# VFan.net
KiCad netlist of a schematic drawn in Altium Designer
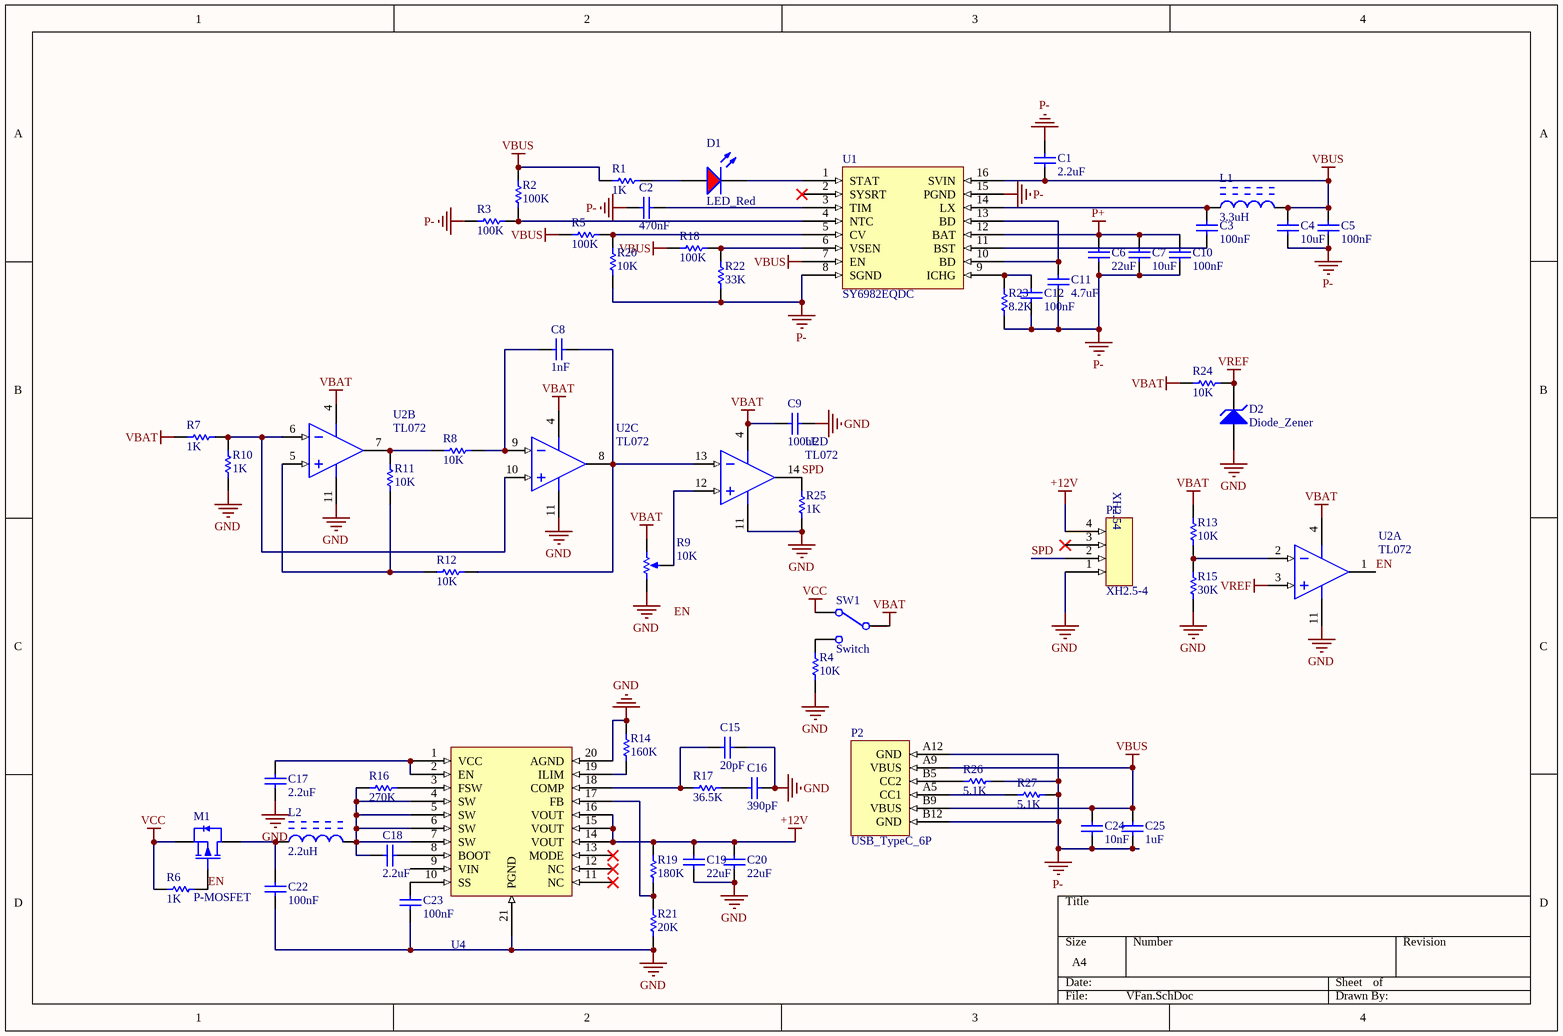
[diagram p0: VFan.SchDoc]

(export (version "E")
  (design (tool "Eeschema 10.0.6"))
  (components
    (comp (ref "C1") (value "2.2uF") (footprint "SMC_0805") (libsource (lib "Common") (part "Cap Ceramic")))
    (comp (ref "C2") (value "470nF") (footprint "SMC_0402") (libsource (lib "Common") (part "Cap Ceramic")))
    (comp (ref "C3") (value "100nF") (footprint "SMC_0402") (libsource (lib "Common") (part "Cap Ceramic")))
    (comp (ref "C4") (value "10uF") (footprint "SMC_0805") (libsource (lib "Common") (part "Cap Ceramic")))
    (comp (ref "C5") (value "100nF") (footprint "SMC_0603") (libsource (lib "Common") (part "Cap Ceramic")))
    (comp (ref "C6") (value "22uF") (footprint "SMC_0805") (libsource (lib "Common") (part "Cap Ceramic")))
    (comp (ref "C7") (value "10uF") (footprint "SMC_0805") (libsource (lib "Common") (part "Cap Ceramic")))
    (comp (ref "C8") (value "1nF") (footprint "SMC_0402") (libsource (lib "Common") (part "Cap Ceramic")))
    (comp (ref "C9") (value "100nF") (footprint "SMC_0402") (libsource (lib "Common") (part "Cap Ceramic")))
    (comp (ref "C10") (value "100nF") (footprint "SMC_0603") (libsource (lib "Common") (part "Cap Ceramic")))
    (comp (ref "C11") (value "4.7uF") (footprint "SMC_0805") (libsource (lib "Common") (part "Cap Ceramic")))
    (comp (ref "C12") (value "100nF") (footprint "SMC_0603") (libsource (lib "Common") (part "Cap Ceramic")))
    (comp (ref "C15") (value "20pF") (footprint "SMC_0402") (libsource (lib "Common") (part "Cap Ceramic")))
    (comp (ref "C16") (value "390pF") (footprint "SMC_0402") (libsource (lib "Common") (part "Cap Ceramic")))
    (comp (ref "C17") (value "2.2uF") (footprint "SMC_0603") (libsource (lib "Common") (part "Cap Ceramic")))
    (comp (ref "C18") (value "2.2uF") (footprint "SMC_0603") (libsource (lib "Common") (part "Cap Ceramic")))
    (comp (ref "C19") (value "22uF") (footprint "SMC_1210") (libsource (lib "Common") (part "Cap Ceramic")))
    (comp (ref "C20") (value "22uF") (footprint "SMC_1210") (libsource (lib "Common") (part "Cap Ceramic")))
    (comp (ref "C22") (value "100nF") (footprint "SMC_0402") (libsource (lib "Common") (part "Cap Ceramic")))
    (comp (ref "C23") (value "100nF") (footprint "SMC_0402") (libsource (lib "Common") (part "Cap Ceramic")))
    (comp (ref "C24") (value "10nF") (footprint "SMC_0402") (libsource (lib "Common") (part "Cap Ceramic")))
    (comp (ref "C25") (value "1uF") (footprint "SMC_0402") (libsource (lib "Common") (part "Cap Ceramic")))
    (comp (ref "D1") (value "LED_Red") (footprint "THLED_3mm") (libsource (lib "Common") (part "LED_Red")))
    (comp (ref "D2")
      (value "Diode_Zener")
      (footprint "SOD-123")
      (libsource (lib "Common") (part "Diode_Zener"))
    )
    (comp (ref "L1")
      (value "3.3uH")
      (footprint "SML_4.1x4.6")
      (libsource (lib "Common") (part "Inductor_Ferrite SMT"))
    )
    (comp (ref "L2")
      (value "2.2uH")
      (footprint "SML_7.4x6.6")
      (libsource (lib "Common") (part "Inductor_Ferrite SMT"))
    )
    (comp (ref "M1")
      (value "P-MOSFET")
      (footprint "SOIC127P600X175-8N")
      (libsource (lib "BJT_MOSFET") (part "P-MOSFET"))
    )
    (comp (ref "P1") (value "XH2.5-4") (footprint "XH2.54-4S") (libsource (lib "Connector") (part "XH2.5-4")))
    (comp (ref "P2")
      (value "USB_TypeC_6P")
      (footprint "USB_TypeC_6P")
      (libsource (lib "Connector") (part "USB_TypeC_6P"))
    )
    (comp (ref "R1") (value "1K") (footprint "SMR_0402") (libsource (lib "Common") (part "Res SMT")))
    (comp (ref "R2") (value "100K") (footprint "SMR_0402") (libsource (lib "Common") (part "Res SMT")))
    (comp (ref "R3") (value "100K") (footprint "SMR_0402") (libsource (lib "Common") (part "Res SMT")))
    (comp (ref "R4") (value "10K") (footprint "SMR_0402") (libsource (lib "Common") (part "Res SMT")))
    (comp (ref "R5") (value "100K") (footprint "SMR_0402") (libsource (lib "Common") (part "Res SMT")))
    (comp (ref "R6") (value "1K") (footprint "SMR_0402") (libsource (lib "Common") (part "Res SMT")))
    (comp (ref "R7") (value "1K") (footprint "SMR_0402") (libsource (lib "Common") (part "Res SMT")))
    (comp (ref "R8") (value "10K") (footprint "SMR_0402") (libsource (lib "Common") (part "Res SMT")))
    (comp (ref "R9") (value "10K") (footprint "RV09032") (libsource (lib "Common") (part "Res Var")))
    (comp (ref "R10") (value "1K") (footprint "SMR_0402") (libsource (lib "Common") (part "Res SMT")))
    (comp (ref "R11") (value "10K") (footprint "SMR_0402") (libsource (lib "Common") (part "Res SMT")))
    (comp (ref "R12") (value "10K") (footprint "SMR_0402") (libsource (lib "Common") (part "Res SMT")))
    (comp (ref "R13") (value "10K") (footprint "SMR_0402") (libsource (lib "Common") (part "Res SMT")))
    (comp (ref "R14") (value "160K") (footprint "SMR_0402") (libsource (lib "Common") (part "Res SMT")))
    (comp (ref "R15") (value "30K") (footprint "SMR_0402") (libsource (lib "Common") (part "Res SMT")))
    (comp (ref "R16") (value "270K") (footprint "SMR_0402") (libsource (lib "Common") (part "Res SMT")))
    (comp (ref "R17") (value "36.5K") (footprint "SMR_0402") (libsource (lib "Common") (part "Res SMT")))
    (comp (ref "R18") (value "100K") (footprint "SMR_0402") (libsource (lib "Common") (part "Res SMT")))
    (comp (ref "R19") (value "180K") (footprint "SMR_0402") (libsource (lib "Common") (part "Res SMT")))
    (comp (ref "R20") (value "10K") (footprint "SMR_0402") (libsource (lib "Common") (part "Res SMT")))
    (comp (ref "R21") (value "20K") (footprint "SMR_0402") (libsource (lib "Common") (part "Res SMT")))
    (comp (ref "R22") (value "33K") (footprint "SMR_0402") (libsource (lib "Common") (part "Res SMT")))
    (comp (ref "R23") (value "8.2K") (footprint "SMR_0402") (libsource (lib "Common") (part "Res SMT")))
    (comp (ref "R24") (value "10K") (footprint "SMR_0402") (libsource (lib "Common") (part "Res SMT")))
    (comp (ref "R25") (value "1K") (footprint "SMR_0402") (libsource (lib "Common") (part "Res SMT")))
    (comp (ref "R26") (value "5.1K") (footprint "SMR_0402") (libsource (lib "Common") (part "Res SMT")))
    (comp (ref "R27") (value "5.1K") (footprint "SMR_0402") (libsource (lib "Common") (part "Res SMT")))
    (comp (ref "SW1") (value "Switch") (footprint "Switch") (libsource (lib "Button_Switch") (part "Switch")))
    (comp (ref "U1")
      (value "SY6982EQDC")
      (footprint "SY6982EQDC")
      (libsource (lib "Charger") (part "SY6982EQDC"))
    )
    (comp (ref "U2")
      (value "TL072")
      (footprint "TSOP65P640X120-14N")
      (libsource (lib "OpAmp") (part "OPA4376"))
    )
    (comp (ref "U4")
      (value "Buck Boost Converter")
      (footprint "QFN50P350X450X100_HS-21N")
      (libsource (lib "PowerManagement") (part "TPS61088"))
    )
  )
  (nets
    (net (code "1") (name "+12V") (class "Default")
      (node (ref "C19") (pin "2") (pinfunction "2_2") (pintype "passive"))
      (node (ref "C20") (pin "2") (pinfunction "2_2") (pintype "passive"))
      (node (ref "P1") (pin "4") (pintype "input"))
      (node (ref "R19") (pin "2") (pinfunction "2_2") (pintype "passive"))
      (node (ref "U4") (pin "14") (pinfunction "VOUT_14") (pintype "input"))
      (node (ref "U4") (pin "15") (pinfunction "VOUT_15") (pintype "input"))
      (node (ref "U4") (pin "16") (pinfunction "VOUT_16") (pintype "input"))
    )
    (net (code "2") (name "/EN") (class "Default")
      (node (ref "M1") (pin "G") (pinfunction "G_G") (pintype "passive"))
      (node (ref "R6") (pin "1") (pinfunction "1_1") (pintype "passive"))
      (node (ref "U2") (pin "1") (pinfunction "OUT_1") (pintype "open_collector"))
    )
    (net (code "3") (name "/SPD") (class "Default")
      (node (ref "P1") (pin "2") (pintype "input"))
      (node (ref "R25") (pin "1") (pinfunction "1_1") (pintype "passive"))
      (node (ref "U2") (pin "14") (pinfunction "OUT_14") (pintype "open_collector"))
    )
    (net (code "4") (name "GND") (class "Default")
      (node (ref "C15") (pin "2") (pinfunction "2_2") (pintype "passive"))
      (node (ref "C16") (pin "2") (pinfunction "2_2") (pintype "passive"))
      (node (ref "C17") (pin "1") (pinfunction "1_1") (pintype "passive"))
      (node (ref "C19") (pin "1") (pinfunction "1_1") (pintype "passive"))
      (node (ref "C20") (pin "1") (pinfunction "1_1") (pintype "passive"))
      (node (ref "C22") (pin "2") (pinfunction "2_2") (pintype "passive"))
      (node (ref "C23") (pin "2") (pinfunction "2_2") (pintype "passive"))
      (node (ref "C9") (pin "2") (pinfunction "2_2") (pintype "passive"))
      (node (ref "D2") (pin "A") (pinfunction "A_A") (pintype "passive"))
      (node (ref "P1") (pin "1") (pintype "input"))
      (node (ref "R10") (pin "1") (pinfunction "1_1") (pintype "passive"))
      (node (ref "R14") (pin "2") (pinfunction "2_2") (pintype "passive"))
      (node (ref "R15") (pin "1") (pinfunction "1_1") (pintype "passive"))
      (node (ref "R21") (pin "1") (pinfunction "1_1") (pintype "passive"))
      (node (ref "R25") (pin "2") (pinfunction "2_2") (pintype "passive"))
      (node (ref "R4") (pin "1") (pinfunction "1_1") (pintype "passive"))
      (node (ref "R9") (pin "1") (pinfunction "TOP_1") (pintype "passive"))
      (node (ref "U2") (pin "11") (pinfunction "V-_11") (pintype "power_in"))
      (node (ref "U4") (pin "20") (pinfunction "AGND_20") (pintype "input"))
      (node (ref "U4") (pin "21") (pinfunction "PGND_21") (pintype "input"))
    )
    (net (code "5") (name "Net-(C11-Pad2)") (class "Default")
      (node (ref "C11") (pin "2") (pinfunction "2_2") (pintype "passive"))
      (node (ref "U1") (pin "10") (pinfunction "BD_10") (pintype "input"))
      (node (ref "U1") (pin "13") (pinfunction "BD_13") (pintype "input"))
    )
    (net (code "6") (name "Net-(C16-Pad1)") (class "Default")
      (node (ref "C16") (pin "1") (pinfunction "1_1") (pintype "passive"))
      (node (ref "R17") (pin "1") (pinfunction "1_1") (pintype "passive"))
    )
    (net (code "7") (name "Net-(C18-Pad2)") (class "Default")
      (node (ref "C18") (pin "2") (pinfunction "2_2") (pintype "passive"))
      (node (ref "L2") (pin "2") (pinfunction "2_2") (pintype "passive"))
      (node (ref "R16") (pin "1") (pinfunction "1_1") (pintype "passive"))
      (node (ref "U4") (pin "4") (pinfunction "SW_4") (pintype "input"))
      (node (ref "U4") (pin "5") (pinfunction "SW_5") (pintype "input"))
      (node (ref "U4") (pin "6") (pinfunction "SW_6") (pintype "input"))
      (node (ref "U4") (pin "7") (pinfunction "SW_7") (pintype "input"))
    )
    (net (code "8") (name "Net-(C22-Pad1)") (class "Default")
      (node (ref "C22") (pin "1") (pinfunction "1_1") (pintype "passive"))
      (node (ref "L2") (pin "1") (pinfunction "1_1") (pintype "passive"))
      (node (ref "M1") (pin "D") (pinfunction "D_D") (pintype "passive"))
    )
    (net (code "9") (name "Net-(D1-PadA)") (class "Default")
      (node (ref "D1") (pin "A") (pinfunction "A_A") (pintype "passive"))
      (node (ref "R1") (pin "1") (pinfunction "1_1") (pintype "passive"))
    )
    (net (code "10") (name "Net-(P2-CC1)") (class "Default")
      (node (ref "P2") (pin "A5") (pinfunction "CC1_A5") (pintype "input"))
      (node (ref "R27") (pin "1") (pinfunction "1_1") (pintype "passive"))
    )
    (net (code "11") (name "Net-(P2-CC2)") (class "Default")
      (node (ref "P2") (pin "B5") (pinfunction "CC2_B5") (pintype "input"))
      (node (ref "R26") (pin "1") (pinfunction "1_1") (pintype "passive"))
    )
    (net (code "12") (name "Net-(R4-Pad2)") (class "Default")
      (node (ref "R4") (pin "2") (pinfunction "2_2") (pintype "passive"))
      (node (ref "SW1") (pin "3") (pinfunction "3_3") (pintype "passive"))
    )
    (net (code "13") (name "Net-(R9-TAP)") (class "Default")
      (node (ref "R9") (pin "2") (pinfunction "TAP_2") (pintype "passive"))
      (node (ref "U2") (pin "12") (pinfunction "IN+_12") (pintype "input"))
    )
    (net (code "14") (name "Net-(U1-BST)") (class "Default")
      (node (ref "C3") (pin "1") (pinfunction "1_1") (pintype "passive"))
      (node (ref "U1") (pin "11") (pinfunction "BST_11") (pintype "input"))
    )
    (net (code "15") (name "Net-(U1-CV)") (class "Default")
      (node (ref "R20") (pin "2") (pinfunction "2_2") (pintype "passive"))
      (node (ref "R5") (pin "1") (pinfunction "1_1") (pintype "passive"))
      (node (ref "U1") (pin "5") (pinfunction "CV_5") (pintype "input"))
    )
    (net (code "16") (name "Net-(U1-ICHG)") (class "Default")
      (node (ref "C12") (pin "2") (pinfunction "2_2") (pintype "passive"))
      (node (ref "R23") (pin "2") (pinfunction "2_2") (pintype "passive"))
      (node (ref "U1") (pin "9") (pinfunction "ICHG_9") (pintype "input"))
    )
    (net (code "17") (name "Net-(U1-LX)") (class "Default")
      (node (ref "C3") (pin "2") (pinfunction "2_2") (pintype "passive"))
      (node (ref "L1") (pin "1") (pinfunction "1_1") (pintype "passive"))
      (node (ref "U1") (pin "14") (pinfunction "LX_14") (pintype "input"))
    )
    (net (code "18") (name "Net-(U1-NTC)") (class "Default")
      (node (ref "R2") (pin "1") (pinfunction "1_1") (pintype "passive"))
      (node (ref "R3") (pin "2") (pinfunction "2_2") (pintype "passive"))
      (node (ref "U1") (pin "4") (pinfunction "NTC_4") (pintype "input"))
    )
    (net (code "19") (name "Net-(U1-STAT)") (class "Default")
      (node (ref "D1") (pin "K") (pinfunction "K_K") (pintype "passive"))
      (node (ref "U1") (pin "1") (pinfunction "STAT_1") (pintype "input"))
    )
    (net (code "20") (name "Net-(U1-TIM)") (class "Default")
      (node (ref "C2") (pin "2") (pinfunction "2_2") (pintype "passive"))
      (node (ref "U1") (pin "3") (pinfunction "TIM_3") (pintype "input"))
    )
    (net (code "21") (name "Net-(U1-VSEN)") (class "Default")
      (node (ref "R18") (pin "1") (pinfunction "1_1") (pintype "passive"))
      (node (ref "R22") (pin "2") (pinfunction "2_2") (pintype "passive"))
      (node (ref "U1") (pin "6") (pinfunction "VSEN_6") (pintype "input"))
    )
    (net (code "22") (name "Net-(U2A-IN-)") (class "Default")
      (node (ref "R13") (pin "1") (pinfunction "1_1") (pintype "passive"))
      (node (ref "R15") (pin "2") (pinfunction "2_2") (pintype "passive"))
      (node (ref "U2") (pin "2") (pinfunction "IN-_2") (pintype "input"))
    )
    (net (code "23") (name "Net-(U2B-IN+)") (class "Default")
      (node (ref "R11") (pin "1") (pinfunction "1_1") (pintype "passive"))
      (node (ref "R12") (pin "1") (pinfunction "1_1") (pintype "passive"))
      (node (ref "U2") (pin "5") (pinfunction "IN+_5") (pintype "input"))
    )
    (net (code "24") (name "Net-(U2B-IN-)") (class "Default")
      (node (ref "R10") (pin "2") (pinfunction "2_2") (pintype "passive"))
      (node (ref "R7") (pin "1") (pinfunction "1_1") (pintype "passive"))
      (node (ref "U2") (pin "10") (pinfunction "IN+_10") (pintype "input"))
      (node (ref "U2") (pin "6") (pinfunction "IN-_6") (pintype "input"))
    )
    (net (code "25") (name "Net-(U2B-OUT)") (class "Default")
      (node (ref "R11") (pin "2") (pinfunction "2_2") (pintype "passive"))
      (node (ref "R8") (pin "1") (pinfunction "1_1") (pintype "passive"))
      (node (ref "U2") (pin "7") (pinfunction "OUT_7") (pintype "open_collector"))
    )
    (net (code "26") (name "Net-(U2C-IN-)") (class "Default")
      (node (ref "C8") (pin "1") (pinfunction "1_1") (pintype "passive"))
      (node (ref "R8") (pin "2") (pinfunction "2_2") (pintype "passive"))
      (node (ref "U2") (pin "9") (pinfunction "IN-_9") (pintype "input"))
    )
    (net (code "27") (name "Net-(U2C-OUT)") (class "Default")
      (node (ref "C8") (pin "2") (pinfunction "2_2") (pintype "passive"))
      (node (ref "R12") (pin "2") (pinfunction "2_2") (pintype "passive"))
      (node (ref "U2") (pin "13") (pinfunction "IN-_13") (pintype "input"))
      (node (ref "U2") (pin "8") (pinfunction "OUT_8") (pintype "open_collector"))
    )
    (net (code "28") (name "Net-(U4-BOOT)") (class "Default")
      (node (ref "C18") (pin "1") (pinfunction "1_1") (pintype "passive"))
      (node (ref "U4") (pin "8") (pinfunction "BOOT_8") (pintype "input"))
    )
    (net (code "29") (name "Net-(U4-COMP)") (class "Default")
      (node (ref "C15") (pin "1") (pinfunction "1_1") (pintype "passive"))
      (node (ref "R17") (pin "2") (pinfunction "2_2") (pintype "passive"))
      (node (ref "U4") (pin "18") (pinfunction "COMP_18") (pintype "input"))
    )
    (net (code "30") (name "Net-(U4-EN)") (class "Default")
      (node (ref "C17") (pin "2") (pinfunction "2_2") (pintype "passive"))
      (node (ref "U4") (pin "1") (pinfunction "VCC_1") (pintype "input"))
      (node (ref "U4") (pin "2") (pinfunction "EN_2") (pintype "input"))
    )
    (net (code "31") (name "Net-(U4-FB)") (class "Default")
      (node (ref "R19") (pin "1") (pinfunction "1_1") (pintype "passive"))
      (node (ref "R21") (pin "2") (pinfunction "2_2") (pintype "passive"))
      (node (ref "U4") (pin "17") (pinfunction "FB_17") (pintype "input"))
    )
    (net (code "32") (name "Net-(U4-FSW)") (class "Default")
      (node (ref "R16") (pin "2") (pinfunction "2_2") (pintype "passive"))
      (node (ref "U4") (pin "3") (pinfunction "FSW_3") (pintype "input"))
    )
    (net (code "33") (name "Net-(U4-ILIM)") (class "Default")
      (node (ref "R14") (pin "1") (pinfunction "1_1") (pintype "passive"))
      (node (ref "U4") (pin "19") (pinfunction "ILIM_19") (pintype "input"))
    )
    (net (code "34") (name "Net-(U4-SS)") (class "Default")
      (node (ref "C23") (pin "1") (pinfunction "1_1") (pintype "passive"))
      (node (ref "U4") (pin "10") (pinfunction "SS_10") (pintype "input"))
    )
    (net (code "35") (name "P+") (class "Default")
      (node (ref "C10") (pin "2") (pinfunction "2_2") (pintype "passive"))
      (node (ref "C6") (pin "2") (pinfunction "2_2") (pintype "passive"))
      (node (ref "C7") (pin "2") (pinfunction "2_2") (pintype "passive"))
      (node (ref "U1") (pin "12") (pinfunction "BAT_12") (pintype "input"))
    )
    (net (code "36") (name "P-") (class "Default")
      (node (ref "C1") (pin "2") (pinfunction "2_2") (pintype "passive"))
      (node (ref "C10") (pin "1") (pinfunction "1_1") (pintype "passive"))
      (node (ref "C11") (pin "1") (pinfunction "1_1") (pintype "passive"))
      (node (ref "C12") (pin "1") (pinfunction "1_1") (pintype "passive"))
      (node (ref "C2") (pin "1") (pinfunction "1_1") (pintype "passive"))
      (node (ref "C24") (pin "1") (pinfunction "1_1") (pintype "passive"))
      (node (ref "C25") (pin "1") (pinfunction "1_1") (pintype "passive"))
      (node (ref "C4") (pin "1") (pinfunction "1_1") (pintype "passive"))
      (node (ref "C5") (pin "1") (pinfunction "1_1") (pintype "passive"))
      (node (ref "C6") (pin "1") (pinfunction "1_1") (pintype "passive"))
      (node (ref "C7") (pin "1") (pinfunction "1_1") (pintype "passive"))
      (node (ref "P2") (pin "A12") (pinfunction "GND_A12") (pintype "input"))
      (node (ref "P2") (pin "B12") (pinfunction "GND_B12") (pintype "input"))
      (node (ref "R20") (pin "1") (pinfunction "1_1") (pintype "passive"))
      (node (ref "R22") (pin "1") (pinfunction "1_1") (pintype "passive"))
      (node (ref "R23") (pin "1") (pinfunction "1_1") (pintype "passive"))
      (node (ref "R26") (pin "2") (pinfunction "2_2") (pintype "passive"))
      (node (ref "R27") (pin "2") (pinfunction "2_2") (pintype "passive"))
      (node (ref "R3") (pin "1") (pinfunction "1_1") (pintype "passive"))
      (node (ref "U1") (pin "15") (pinfunction "PGND_15") (pintype "input"))
      (node (ref "U1") (pin "8") (pinfunction "SGND_8") (pintype "input"))
    )
    (net (code "37") (name "VBAT") (class "Default")
      (node (ref "C9") (pin "1") (pinfunction "1_1") (pintype "passive"))
      (node (ref "R13") (pin "2") (pinfunction "2_2") (pintype "passive"))
      (node (ref "R24") (pin "2") (pinfunction "2_2") (pintype "passive"))
      (node (ref "R7") (pin "2") (pinfunction "2_2") (pintype "passive"))
      (node (ref "R9") (pin "3") (pinfunction "BOT_3") (pintype "passive"))
      (node (ref "SW1") (pin "1") (pinfunction "1_1") (pintype "passive"))
      (node (ref "U2") (pin "4") (pinfunction "V+_4") (pintype "power_in"))
    )
    (net (code "38") (name "VBUS") (class "Default")
      (node (ref "C1") (pin "1") (pinfunction "1_1") (pintype "passive"))
      (node (ref "C24") (pin "2") (pinfunction "2_2") (pintype "passive"))
      (node (ref "C25") (pin "2") (pinfunction "2_2") (pintype "passive"))
      (node (ref "C4") (pin "2") (pinfunction "2_2") (pintype "passive"))
      (node (ref "C5") (pin "2") (pinfunction "2_2") (pintype "passive"))
      (node (ref "L1") (pin "2") (pinfunction "2_2") (pintype "passive"))
      (node (ref "P2") (pin "A9") (pinfunction "VBUS_A9") (pintype "input"))
      (node (ref "P2") (pin "B9") (pinfunction "VBUS_B9") (pintype "input"))
      (node (ref "R1") (pin "2") (pinfunction "2_2") (pintype "passive"))
      (node (ref "R18") (pin "2") (pinfunction "2_2") (pintype "passive"))
      (node (ref "R2") (pin "2") (pinfunction "2_2") (pintype "passive"))
      (node (ref "R5") (pin "2") (pinfunction "2_2") (pintype "passive"))
      (node (ref "U1") (pin "16") (pinfunction "SVIN_16") (pintype "input"))
      (node (ref "U1") (pin "7") (pinfunction "EN_7") (pintype "input"))
    )
    (net (code "39") (name "VCC") (class "Default")
      (node (ref "M1") (pin "S") (pinfunction "S_S") (pintype "passive"))
      (node (ref "R6") (pin "2") (pinfunction "2_2") (pintype "passive"))
      (node (ref "SW1") (pin "2") (pinfunction "2_2") (pintype "passive"))
    )
    (net (code "40") (name "VREF") (class "Default")
      (node (ref "D2") (pin "K") (pinfunction "K_K") (pintype "passive"))
      (node (ref "R24") (pin "1") (pinfunction "1_1") (pintype "passive"))
      (node (ref "U2") (pin "3") (pinfunction "IN+_3") (pintype "input"))
    )
    (net (code "41") (name "unconnected-(P1-Pad3)") (class "Default")
      (node (ref "P1") (pin "3") (pintype "input+no_connect"))
    )
    (net (code "42") (name "unconnected-(U1-SYSRT-Pad2)") (class "Default")
      (node (ref "U1") (pin "2") (pinfunction "SYSRT_2") (pintype "input+no_connect"))
    )
    (net (code "43") (name "unconnected-(U2B-V+-Pad4)") (class "Default")
      (node (ref "U2") (pin "4") (pinfunction "V+_4") (pintype "power_in"))
    )
    (net (code "44") (name "unconnected-(U4-MODE-Pad13)") (class "Default")
      (node (ref "U4") (pin "13") (pinfunction "MODE_13") (pintype "input+no_connect"))
    )
    (net (code "45") (name "unconnected-(U4-NC-Pad11)") (class "Default")
      (node (ref "U4") (pin "11") (pinfunction "NC_11") (pintype "input+no_connect"))
    )
    (net (code "46") (name "unconnected-(U4-NC-Pad12)") (class "Default")
      (node (ref "U4") (pin "12") (pinfunction "NC_12") (pintype "input+no_connect"))
    )
    (net (code "47") (name "unconnected-(U4-VIN-Pad9)") (class "Default")
      (node (ref "U4") (pin "9") (pinfunction "VIN_9") (pintype "input"))
    )
  )
)
